# Arduino-Shield.net
KiCad netlist of a schematic drawn in EAGLE
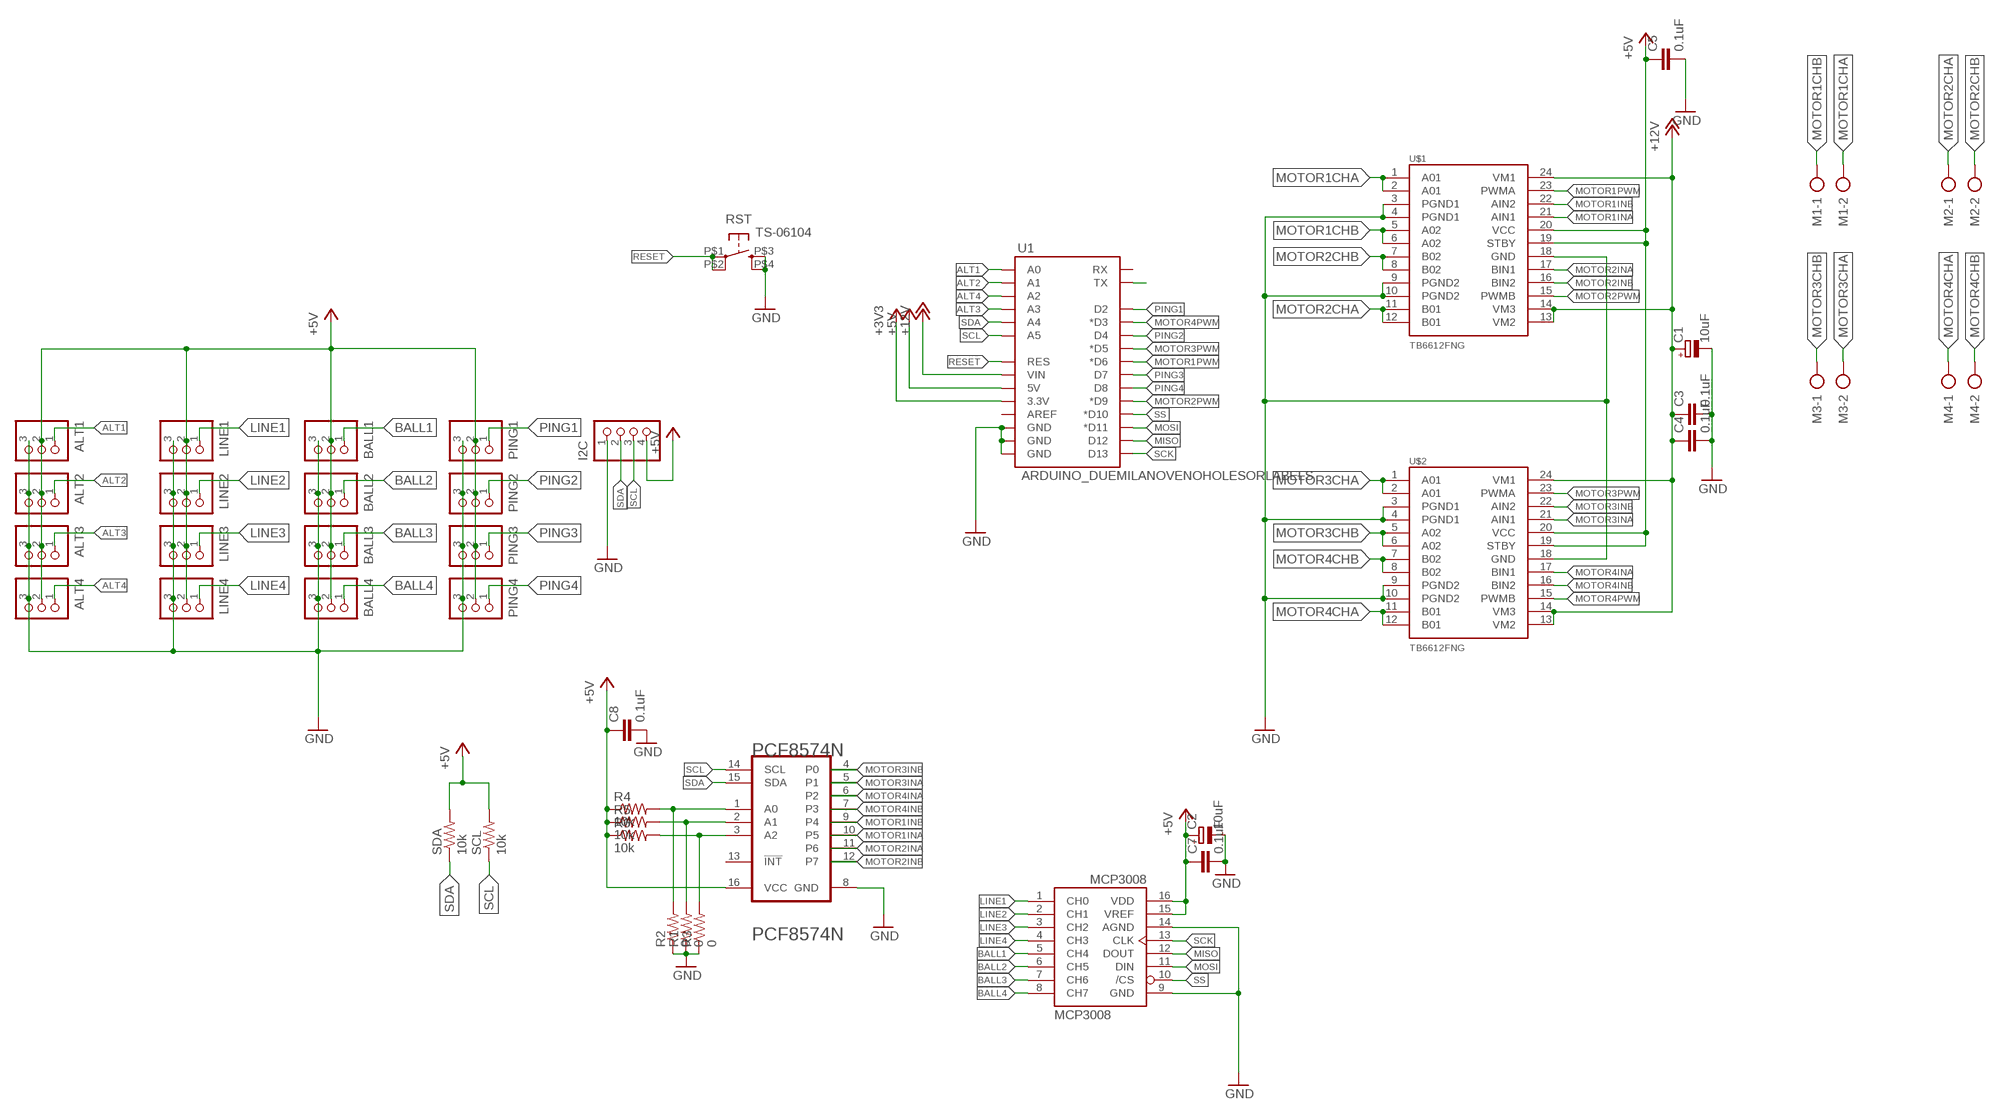
[diagram p0: schematic, sheet 1]

(export (version "E")
  (design (tool "Eeschema 10.0.6"))
  (components
    (comp (ref "ALT1")
      (value "B3B-XH-A")
      (footprint "eagle-import:B3B-XH-A")
      (libsource (lib "eagle-import") (part "B3B-XH-A"))
    )
    (comp (ref "ALT2")
      (value "B3B-XH-A")
      (footprint "eagle-import:B3B-XH-A")
      (libsource (lib "eagle-import") (part "B3B-XH-A"))
    )
    (comp (ref "ALT3")
      (value "B3B-XH-A")
      (footprint "eagle-import:B3B-XH-A")
      (libsource (lib "eagle-import") (part "B3B-XH-A"))
    )
    (comp (ref "ALT4")
      (value "B3B-XH-A")
      (footprint "eagle-import:B3B-XH-A")
      (libsource (lib "eagle-import") (part "B3B-XH-A"))
    )
    (comp (ref "BALL1")
      (value "B3B-XH-A")
      (footprint "eagle-import:B3B-XH-A")
      (libsource (lib "eagle-import") (part "B3B-XH-A"))
    )
    (comp (ref "BALL2")
      (value "B3B-XH-A")
      (footprint "eagle-import:B3B-XH-A")
      (libsource (lib "eagle-import") (part "B3B-XH-A"))
    )
    (comp (ref "BALL3")
      (value "B3B-XH-A")
      (footprint "eagle-import:B3B-XH-A")
      (libsource (lib "eagle-import") (part "B3B-XH-A"))
    )
    (comp (ref "BALL4")
      (value "B3B-XH-A")
      (footprint "eagle-import:B3B-XH-A")
      (libsource (lib "eagle-import") (part "B3B-XH-A"))
    )
    (comp (ref "C1")
      (value "10uF")
      (footprint "eagle-import:E2-5")
      (libsource (lib "eagle-import") (part "CPOL-EUE2-5"))
    )
    (comp (ref "C2")
      (value "10uF")
      (footprint "eagle-import:E2-5")
      (libsource (lib "eagle-import") (part "CPOL-EUE2-5"))
    )
    (comp (ref "C3")
      (value "0.1uF")
      (footprint "eagle-import:C1608")
      (libsource (lib "eagle-import") (part "C-EUC1608"))
    )
    (comp (ref "C4")
      (value "0.1uF")
      (footprint "eagle-import:C1608")
      (libsource (lib "eagle-import") (part "C-EUC1608"))
    )
    (comp (ref "C5")
      (value "0.1uF")
      (footprint "eagle-import:C1608")
      (libsource (lib "eagle-import") (part "C-EUC1608"))
    )
    (comp (ref "C7")
      (value "0.1uF")
      (footprint "eagle-import:C1608")
      (libsource (lib "eagle-import") (part "C-EUC1608"))
    )
    (comp (ref "C8")
      (value "0.1uF")
      (footprint "eagle-import:C1608")
      (libsource (lib "eagle-import") (part "C-EUC1608"))
    )
    (comp (ref "I2C")
      (value "B4B-XH-A")
      (footprint "eagle-import:B4B-XH-A")
      (libsource (lib "eagle-import") (part "B4B-XH-A"))
    )
    (comp (ref "LINE1")
      (value "B3B-XH-A")
      (footprint "eagle-import:B3B-XH-A")
      (libsource (lib "eagle-import") (part "B3B-XH-A"))
    )
    (comp (ref "LINE2")
      (value "B3B-XH-A")
      (footprint "eagle-import:B3B-XH-A")
      (libsource (lib "eagle-import") (part "B3B-XH-A"))
    )
    (comp (ref "LINE3")
      (value "B3B-XH-A")
      (footprint "eagle-import:B3B-XH-A")
      (libsource (lib "eagle-import") (part "B3B-XH-A"))
    )
    (comp (ref "LINE4")
      (value "B3B-XH-A")
      (footprint "eagle-import:B3B-XH-A")
      (libsource (lib "eagle-import") (part "B3B-XH-A"))
    )
    (comp (ref "M1")
      (value "AK500/2-H")
      (footprint "eagle-import:AK500_2-H")
      (libsource (lib "eagle-import") (part "AK500/2-H"))
    )
    (comp (ref "M2")
      (value "AK500/2-H")
      (footprint "eagle-import:AK500_2-H")
      (libsource (lib "eagle-import") (part "AK500/2-H"))
    )
    (comp (ref "M3")
      (value "AK500/2-H")
      (footprint "eagle-import:AK500_2-H")
      (libsource (lib "eagle-import") (part "AK500/2-H"))
    )
    (comp (ref "M4")
      (value "AK500/2-H")
      (footprint "eagle-import:AK500_2-H")
      (libsource (lib "eagle-import") (part "AK500/2-H"))
    )
    (comp (ref "MCP3008")
      (value "MCP3008")
      (footprint "eagle-import:DIL16")
      (libsource (lib "eagle-import") (part "MCP3008"))
    )
    (comp (ref "PCF8574N")
      (value "TEXAS_INSTRUMENTS_PCF8574NTEXAS_INSTRUMENTS_PCF8574N_0_0")
      (footprint "eagle-import:TEXAS_INSTRUMENTS_PCF8574N_0")
      (fields (field (name "MF") "Texas Instruments") (field (name "MPN") "PCF8574N"))
      (libsource (lib "eagle-import") (part "TEXAS_INSTRUMENTS_PCF8574NTEXAS_INSTRUMENTS_PCF8574N_0_0"))
    )
    (comp (ref "PING1")
      (value "B3B-XH-A")
      (footprint "eagle-import:B3B-XH-A")
      (libsource (lib "eagle-import") (part "B3B-XH-A"))
    )
    (comp (ref "PING2")
      (value "B3B-XH-A")
      (footprint "eagle-import:B3B-XH-A")
      (libsource (lib "eagle-import") (part "B3B-XH-A"))
    )
    (comp (ref "PING3")
      (value "B3B-XH-A")
      (footprint "eagle-import:B3B-XH-A")
      (libsource (lib "eagle-import") (part "B3B-XH-A"))
    )
    (comp (ref "PING4")
      (value "B3B-XH-A")
      (footprint "eagle-import:B3B-XH-A")
      (libsource (lib "eagle-import") (part "B3B-XH-A"))
    )
    (comp (ref "R1")
      (value "0")
      (footprint "eagle-import:M2012")
      (libsource (lib "eagle-import") (part "R-US_M2012"))
    )
    (comp (ref "R2")
      (value "0")
      (footprint "eagle-import:M2012")
      (libsource (lib "eagle-import") (part "R-US_M2012"))
    )
    (comp (ref "R3")
      (value "0")
      (footprint "eagle-import:M2012")
      (libsource (lib "eagle-import") (part "R-US_M2012"))
    )
    (comp (ref "R4")
      (value "10k")
      (footprint "eagle-import:R0603")
      (libsource (lib "eagle-import") (part "R-US_R0603"))
    )
    (comp (ref "R5")
      (value "10k")
      (footprint "eagle-import:R0603")
      (libsource (lib "eagle-import") (part "R-US_R0603"))
    )
    (comp (ref "R6")
      (value "10k")
      (footprint "eagle-import:R0603")
      (libsource (lib "eagle-import") (part "R-US_R0603"))
    )
    (comp (ref "RST")
      (value "TS-06104")
      (footprint "eagle-import:TS-06104")
      (libsource (lib "eagle-import") (part "TS-06104"))
    )
    (comp (ref "SCL")
      (value "10k")
      (footprint "eagle-import:R0603")
      (libsource (lib "eagle-import") (part "R-US_R0603"))
    )
    (comp (ref "SDA")
      (value "10k")
      (footprint "eagle-import:R0603")
      (libsource (lib "eagle-import") (part "R-US_R0603"))
    )
    (comp (ref "U$1")
      (value "TB6612FNG")
      (footprint "eagle-import:SSOP24")
      (libsource (lib "eagle-import") (part "TB6612FNG"))
    )
    (comp (ref "U$2")
      (value "TB6612FNG")
      (footprint "eagle-import:SSOP24")
      (libsource (lib "eagle-import") (part "TB6612FNG"))
    )
    (comp (ref "U1")
      (value "ARDUINO_DUEMILANOVENOHOLESORLABELS")
      (footprint "eagle-import:DUEMILANOVE_SHIELD_NOHOLES_NOLABELS")
      (libsource (lib "eagle-import") (part "ARDUINO_DUEMILANOVENOHOLESORLABELS"))
    )
  )
  (nets
    (net (code "1") (name "+3V3") (class "Default")
      (node (ref "U1") (pin "3.3V") (pinfunction "3.3V_3.3V") (pintype "bidirectional"))
    )
    (net (code "2") (name "+5V") (class "Default")
      (node (ref "ALT1") (pin "2") (pinfunction "2_2") (pintype "passive"))
      (node (ref "ALT2") (pin "2") (pinfunction "2_2") (pintype "passive"))
      (node (ref "ALT3") (pin "2") (pinfunction "2_2") (pintype "passive"))
      (node (ref "ALT4") (pin "2") (pinfunction "2_2") (pintype "passive"))
      (node (ref "BALL1") (pin "2") (pinfunction "2_2") (pintype "passive"))
      (node (ref "BALL2") (pin "2") (pinfunction "2_2") (pintype "passive"))
      (node (ref "BALL3") (pin "2") (pinfunction "2_2") (pintype "passive"))
      (node (ref "BALL4") (pin "2") (pinfunction "2_2") (pintype "passive"))
      (node (ref "C2") (pin "+") (pinfunction "+_+") (pintype "passive"))
      (node (ref "C5") (pin "1") (pinfunction "1_1") (pintype "passive"))
      (node (ref "C7") (pin "1") (pinfunction "1_1") (pintype "passive"))
      (node (ref "C8") (pin "1") (pinfunction "1_1") (pintype "passive"))
      (node (ref "I2C") (pin "4") (pinfunction "4_4") (pintype "passive"))
      (node (ref "LINE1") (pin "2") (pinfunction "2_2") (pintype "passive"))
      (node (ref "LINE2") (pin "2") (pinfunction "2_2") (pintype "passive"))
      (node (ref "LINE3") (pin "2") (pinfunction "2_2") (pintype "passive"))
      (node (ref "LINE4") (pin "2") (pinfunction "2_2") (pintype "passive"))
      (node (ref "MCP3008") (pin "15") (pinfunction "VREF_15") (pintype "input"))
      (node (ref "MCP3008") (pin "16") (pinfunction "VDD_16") (pintype "power_in"))
      (node (ref "PCF8574N") (pin "16") (pinfunction "VCC_16") (pintype "power_in"))
      (node (ref "PING1") (pin "2") (pinfunction "2_2") (pintype "passive"))
      (node (ref "PING2") (pin "2") (pinfunction "2_2") (pintype "passive"))
      (node (ref "PING3") (pin "2") (pinfunction "2_2") (pintype "passive"))
      (node (ref "PING4") (pin "2") (pinfunction "2_2") (pintype "passive"))
      (node (ref "R4") (pin "1") (pinfunction "1_1") (pintype "passive"))
      (node (ref "R5") (pin "1") (pinfunction "1_1") (pintype "passive"))
      (node (ref "R6") (pin "1") (pinfunction "1_1") (pintype "passive"))
      (node (ref "SCL") (pin "2") (pinfunction "2_2") (pintype "passive"))
      (node (ref "SDA") (pin "2") (pinfunction "2_2") (pintype "passive"))
      (node (ref "U$1") (pin "19") (pinfunction "STBY_19") (pintype "bidirectional"))
      (node (ref "U$1") (pin "20") (pinfunction "VCC_20") (pintype "bidirectional"))
      (node (ref "U$2") (pin "19") (pinfunction "STBY_19") (pintype "bidirectional"))
      (node (ref "U$2") (pin "20") (pinfunction "VCC_20") (pintype "bidirectional"))
      (node (ref "U1") (pin "5V") (pinfunction "5V_5V") (pintype "bidirectional"))
    )
    (net (code "3") (name "+12V") (class "Default")
      (node (ref "C1") (pin "+") (pinfunction "+_+") (pintype "passive"))
      (node (ref "C3") (pin "1") (pinfunction "1_1") (pintype "passive"))
      (node (ref "C4") (pin "1") (pinfunction "1_1") (pintype "passive"))
      (node (ref "U$1") (pin "13") (pinfunction "VM2_13") (pintype "bidirectional"))
      (node (ref "U$1") (pin "14") (pinfunction "VM3_14") (pintype "bidirectional"))
      (node (ref "U$1") (pin "24") (pinfunction "VM1_24") (pintype "bidirectional"))
      (node (ref "U$2") (pin "13") (pinfunction "VM2_13") (pintype "bidirectional"))
      (node (ref "U$2") (pin "14") (pinfunction "VM3_14") (pintype "bidirectional"))
      (node (ref "U$2") (pin "24") (pinfunction "VM1_24") (pintype "bidirectional"))
      (node (ref "U1") (pin "VIN") (pinfunction "VIN_VIN") (pintype "bidirectional"))
    )
    (net (code "4") (name "ALT1") (class "Default")
      (node (ref "ALT1") (pin "1") (pinfunction "1_1") (pintype "passive"))
      (node (ref "U1") (pin "A0") (pinfunction "A0_A0") (pintype "bidirectional"))
    )
    (net (code "5") (name "ALT2") (class "Default")
      (node (ref "ALT2") (pin "1") (pinfunction "1_1") (pintype "passive"))
      (node (ref "U1") (pin "A1") (pinfunction "A1_A1") (pintype "bidirectional"))
    )
    (net (code "6") (name "ALT3") (class "Default")
      (node (ref "ALT3") (pin "1") (pinfunction "1_1") (pintype "passive"))
      (node (ref "U1") (pin "A3") (pinfunction "A3_A3") (pintype "bidirectional"))
    )
    (net (code "7") (name "ALT4") (class "Default")
      (node (ref "ALT4") (pin "1") (pinfunction "1_1") (pintype "passive"))
      (node (ref "U1") (pin "A2") (pinfunction "A2_A2") (pintype "bidirectional"))
    )
    (net (code "8") (name "BALL1") (class "Default")
      (node (ref "BALL1") (pin "1") (pinfunction "1_1") (pintype "passive"))
      (node (ref "MCP3008") (pin "5") (pinfunction "CH4_5") (pintype "input"))
    )
    (net (code "9") (name "BALL2") (class "Default")
      (node (ref "BALL2") (pin "1") (pinfunction "1_1") (pintype "passive"))
      (node (ref "MCP3008") (pin "6") (pinfunction "CH5_6") (pintype "input"))
    )
    (net (code "10") (name "BALL3") (class "Default")
      (node (ref "BALL3") (pin "1") (pinfunction "1_1") (pintype "passive"))
      (node (ref "MCP3008") (pin "7") (pinfunction "CH6_7") (pintype "input"))
    )
    (net (code "11") (name "BALL4") (class "Default")
      (node (ref "BALL4") (pin "1") (pinfunction "1_1") (pintype "passive"))
      (node (ref "MCP3008") (pin "8") (pinfunction "CH7_8") (pintype "input"))
    )
    (net (code "12") (name "GND") (class "Default")
      (node (ref "ALT1") (pin "3") (pinfunction "3_3") (pintype "passive"))
      (node (ref "ALT2") (pin "3") (pinfunction "3_3") (pintype "passive"))
      (node (ref "ALT3") (pin "3") (pinfunction "3_3") (pintype "passive"))
      (node (ref "ALT4") (pin "3") (pinfunction "3_3") (pintype "passive"))
      (node (ref "BALL1") (pin "3") (pinfunction "3_3") (pintype "passive"))
      (node (ref "BALL2") (pin "3") (pinfunction "3_3") (pintype "passive"))
      (node (ref "BALL3") (pin "3") (pinfunction "3_3") (pintype "passive"))
      (node (ref "BALL4") (pin "3") (pinfunction "3_3") (pintype "passive"))
      (node (ref "C1") (pin "-") (pinfunction "-_-") (pintype "passive"))
      (node (ref "C2") (pin "-") (pinfunction "-_-") (pintype "passive"))
      (node (ref "C3") (pin "2") (pinfunction "2_2") (pintype "passive"))
      (node (ref "C4") (pin "2") (pinfunction "2_2") (pintype "passive"))
      (node (ref "C5") (pin "2") (pinfunction "2_2") (pintype "passive"))
      (node (ref "C7") (pin "2") (pinfunction "2_2") (pintype "passive"))
      (node (ref "C8") (pin "2") (pinfunction "2_2") (pintype "passive"))
      (node (ref "I2C") (pin "1") (pinfunction "1_1") (pintype "passive"))
      (node (ref "LINE1") (pin "3") (pinfunction "3_3") (pintype "passive"))
      (node (ref "LINE2") (pin "3") (pinfunction "3_3") (pintype "passive"))
      (node (ref "LINE3") (pin "3") (pinfunction "3_3") (pintype "passive"))
      (node (ref "LINE4") (pin "3") (pinfunction "3_3") (pintype "passive"))
      (node (ref "MCP3008") (pin "14") (pinfunction "AGND_14") (pintype "power_in"))
      (node (ref "MCP3008") (pin "9") (pinfunction "GND_9") (pintype "power_in"))
      (node (ref "PCF8574N") (pin "8") (pinfunction "GND_8") (pintype "power_in"))
      (node (ref "PING1") (pin "3") (pinfunction "3_3") (pintype "passive"))
      (node (ref "PING2") (pin "3") (pinfunction "3_3") (pintype "passive"))
      (node (ref "PING3") (pin "3") (pinfunction "3_3") (pintype "passive"))
      (node (ref "PING4") (pin "3") (pinfunction "3_3") (pintype "passive"))
      (node (ref "R1") (pin "1") (pinfunction "1_1") (pintype "passive"))
      (node (ref "R2") (pin "1") (pinfunction "1_1") (pintype "passive"))
      (node (ref "R3") (pin "1") (pinfunction "1_1") (pintype "passive"))
      (node (ref "RST") (pin "P$3") (pinfunction "3_P$3") (pintype "passive"))
      (node (ref "RST") (pin "P$4") (pinfunction "4_P$4") (pintype "passive"))
      (node (ref "U$1") (pin "10") (pinfunction "PGND2_10") (pintype "bidirectional"))
      (node (ref "U$1") (pin "18") (pinfunction "GND_18") (pintype "bidirectional"))
      (node (ref "U$1") (pin "3") (pinfunction "PGND1_3") (pintype "bidirectional"))
      (node (ref "U$1") (pin "4") (pinfunction "PGND1_4") (pintype "bidirectional"))
      (node (ref "U$1") (pin "9") (pinfunction "PGND2_9") (pintype "bidirectional"))
      (node (ref "U$2") (pin "10") (pinfunction "PGND2_10") (pintype "bidirectional"))
      (node (ref "U$2") (pin "18") (pinfunction "GND_18") (pintype "bidirectional"))
      (node (ref "U$2") (pin "3") (pinfunction "PGND1_3") (pintype "bidirectional"))
      (node (ref "U$2") (pin "4") (pinfunction "PGND1_4") (pintype "bidirectional"))
      (node (ref "U$2") (pin "9") (pinfunction "PGND2_9") (pintype "bidirectional"))
      (node (ref "U1") (pin "GND@0") (pinfunction "GND_GND@0") (pintype "bidirectional"))
      (node (ref "U1") (pin "GND@1") (pinfunction "GND_GND@1") (pintype "bidirectional"))
      (node (ref "U1") (pin "GND@2") (pinfunction "GND_GND@2") (pintype "bidirectional"))
    )
    (net (code "13") (name "LINE1") (class "Default")
      (node (ref "LINE1") (pin "1") (pinfunction "1_1") (pintype "passive"))
      (node (ref "MCP3008") (pin "1") (pinfunction "CH0_1") (pintype "input"))
    )
    (net (code "14") (name "LINE2") (class "Default")
      (node (ref "LINE2") (pin "1") (pinfunction "1_1") (pintype "passive"))
      (node (ref "MCP3008") (pin "2") (pinfunction "CH1_2") (pintype "input"))
    )
    (net (code "15") (name "LINE3") (class "Default")
      (node (ref "LINE3") (pin "1") (pinfunction "1_1") (pintype "passive"))
      (node (ref "MCP3008") (pin "3") (pinfunction "CH2_3") (pintype "input"))
    )
    (net (code "16") (name "LINE4") (class "Default")
      (node (ref "LINE4") (pin "1") (pinfunction "1_1") (pintype "passive"))
      (node (ref "MCP3008") (pin "4") (pinfunction "CH3_4") (pintype "input"))
    )
    (net (code "17") (name "MISO") (class "Default")
      (node (ref "MCP3008") (pin "12") (pinfunction "DOUT_12") (pintype "output"))
      (node (ref "U1") (pin "D12") (pinfunction "D12_D12") (pintype "bidirectional"))
    )
    (net (code "18") (name "MOSI") (class "Default")
      (node (ref "MCP3008") (pin "11") (pinfunction "DIN_11") (pintype "input"))
      (node (ref "U1") (pin "D11") (pinfunction "*D11_D11") (pintype "bidirectional"))
    )
    (net (code "19") (name "MOTOR1CHA") (class "Default")
      (node (ref "M1") (pin "2") (pinfunction "KL_2") (pintype "passive"))
      (node (ref "U$1") (pin "1") (pinfunction "A01_1") (pintype "bidirectional"))
      (node (ref "U$1") (pin "2") (pinfunction "A01_2") (pintype "bidirectional"))
    )
    (net (code "20") (name "MOTOR1CHB") (class "Default")
      (node (ref "M1") (pin "1") (pinfunction "KL_1") (pintype "passive"))
      (node (ref "U$1") (pin "5") (pinfunction "A02_5") (pintype "bidirectional"))
      (node (ref "U$1") (pin "6") (pinfunction "A02_6") (pintype "bidirectional"))
    )
    (net (code "21") (name "MOTOR1INA") (class "Default")
      (node (ref "PCF8574N") (pin "10") (pinfunction "P5_10") (pintype "bidirectional"))
      (node (ref "U$1") (pin "21") (pinfunction "AIN1_21") (pintype "bidirectional"))
    )
    (net (code "22") (name "MOTOR1INB") (class "Default")
      (node (ref "PCF8574N") (pin "9") (pinfunction "P4_9") (pintype "bidirectional"))
      (node (ref "U$1") (pin "22") (pinfunction "AIN2_22") (pintype "bidirectional"))
    )
    (net (code "23") (name "MOTOR1PWM") (class "Default")
      (node (ref "U$1") (pin "23") (pinfunction "PWMA_23") (pintype "bidirectional"))
      (node (ref "U1") (pin "D6") (pinfunction "*D6_D6") (pintype "bidirectional"))
    )
    (net (code "24") (name "MOTOR2CHA") (class "Default")
      (node (ref "M2") (pin "1") (pinfunction "KL_1") (pintype "passive"))
      (node (ref "U$1") (pin "11") (pinfunction "B01_11") (pintype "bidirectional"))
      (node (ref "U$1") (pin "12") (pinfunction "B01_12") (pintype "bidirectional"))
    )
    (net (code "25") (name "MOTOR2CHB") (class "Default")
      (node (ref "M2") (pin "2") (pinfunction "KL_2") (pintype "passive"))
      (node (ref "U$1") (pin "7") (pinfunction "B02_7") (pintype "bidirectional"))
      (node (ref "U$1") (pin "8") (pinfunction "B02_8") (pintype "bidirectional"))
    )
    (net (code "26") (name "MOTOR2INA") (class "Default")
      (node (ref "PCF8574N") (pin "11") (pinfunction "P6_11") (pintype "bidirectional"))
      (node (ref "U$1") (pin "17") (pinfunction "BIN1_17") (pintype "bidirectional"))
    )
    (net (code "27") (name "MOTOR2INB") (class "Default")
      (node (ref "PCF8574N") (pin "12") (pinfunction "P7_12") (pintype "bidirectional"))
      (node (ref "U$1") (pin "16") (pinfunction "BIN2_16") (pintype "bidirectional"))
    )
    (net (code "28") (name "MOTOR2PWM") (class "Default")
      (node (ref "U$1") (pin "15") (pinfunction "PWMB_15") (pintype "bidirectional"))
      (node (ref "U1") (pin "D9") (pinfunction "*D9_D9") (pintype "bidirectional"))
    )
    (net (code "29") (name "MOTOR3CHA") (class "Default")
      (node (ref "M3") (pin "2") (pinfunction "KL_2") (pintype "passive"))
      (node (ref "U$2") (pin "1") (pinfunction "A01_1") (pintype "bidirectional"))
      (node (ref "U$2") (pin "2") (pinfunction "A01_2") (pintype "bidirectional"))
    )
    (net (code "30") (name "MOTOR3CHB") (class "Default")
      (node (ref "M3") (pin "1") (pinfunction "KL_1") (pintype "passive"))
      (node (ref "U$2") (pin "5") (pinfunction "A02_5") (pintype "bidirectional"))
      (node (ref "U$2") (pin "6") (pinfunction "A02_6") (pintype "bidirectional"))
    )
    (net (code "31") (name "MOTOR3INA") (class "Default")
      (node (ref "PCF8574N") (pin "5") (pinfunction "P1_5") (pintype "bidirectional"))
      (node (ref "U$2") (pin "21") (pinfunction "AIN1_21") (pintype "bidirectional"))
    )
    (net (code "32") (name "MOTOR3INB") (class "Default")
      (node (ref "PCF8574N") (pin "4") (pinfunction "P0_4") (pintype "bidirectional"))
      (node (ref "U$2") (pin "22") (pinfunction "AIN2_22") (pintype "bidirectional"))
    )
    (net (code "33") (name "MOTOR3PWM") (class "Default")
      (node (ref "U$2") (pin "23") (pinfunction "PWMA_23") (pintype "bidirectional"))
      (node (ref "U1") (pin "D5") (pinfunction "*D5_D5") (pintype "bidirectional"))
    )
    (net (code "34") (name "MOTOR4CHA") (class "Default")
      (node (ref "M4") (pin "1") (pinfunction "KL_1") (pintype "passive"))
      (node (ref "U$2") (pin "11") (pinfunction "B01_11") (pintype "bidirectional"))
      (node (ref "U$2") (pin "12") (pinfunction "B01_12") (pintype "bidirectional"))
    )
    (net (code "35") (name "MOTOR4CHB") (class "Default")
      (node (ref "M4") (pin "2") (pinfunction "KL_2") (pintype "passive"))
      (node (ref "U$2") (pin "7") (pinfunction "B02_7") (pintype "bidirectional"))
      (node (ref "U$2") (pin "8") (pinfunction "B02_8") (pintype "bidirectional"))
    )
    (net (code "36") (name "MOTOR4INA") (class "Default")
      (node (ref "PCF8574N") (pin "6") (pinfunction "P2_6") (pintype "bidirectional"))
      (node (ref "U$2") (pin "17") (pinfunction "BIN1_17") (pintype "bidirectional"))
    )
    (net (code "37") (name "MOTOR4INB") (class "Default")
      (node (ref "PCF8574N") (pin "7") (pinfunction "P3_7") (pintype "bidirectional"))
      (node (ref "U$2") (pin "16") (pinfunction "BIN2_16") (pintype "bidirectional"))
    )
    (net (code "38") (name "MOTOR4PWM") (class "Default")
      (node (ref "U$2") (pin "15") (pinfunction "PWMB_15") (pintype "bidirectional"))
      (node (ref "U1") (pin "D3") (pinfunction "*D3_D3") (pintype "bidirectional"))
    )
    (net (code "39") (name "Net-(PCF8574N-A0)") (class "Default")
      (node (ref "PCF8574N") (pin "1") (pinfunction "A0_1") (pintype "input"))
      (node (ref "R2") (pin "2") (pinfunction "2_2") (pintype "passive"))
      (node (ref "R4") (pin "2") (pinfunction "2_2") (pintype "passive"))
    )
    (net (code "40") (name "Net-(PCF8574N-A1)") (class "Default")
      (node (ref "PCF8574N") (pin "2") (pinfunction "A1_2") (pintype "input"))
      (node (ref "R1") (pin "2") (pinfunction "2_2") (pintype "passive"))
      (node (ref "R5") (pin "2") (pinfunction "2_2") (pintype "passive"))
    )
    (net (code "41") (name "Net-(PCF8574N-A2)") (class "Default")
      (node (ref "PCF8574N") (pin "3") (pinfunction "A2_3") (pintype "input"))
      (node (ref "R3") (pin "2") (pinfunction "2_2") (pintype "passive"))
      (node (ref "R6") (pin "2") (pinfunction "2_2") (pintype "passive"))
    )
    (net (code "42") (name "PING1") (class "Default")
      (node (ref "PING1") (pin "1") (pinfunction "1_1") (pintype "passive"))
      (node (ref "U1") (pin "D2") (pinfunction "D2_D2") (pintype "bidirectional"))
    )
    (net (code "43") (name "PING2") (class "Default")
      (node (ref "PING2") (pin "1") (pinfunction "1_1") (pintype "passive"))
      (node (ref "U1") (pin "D4") (pinfunction "D4_D4") (pintype "bidirectional"))
    )
    (net (code "44") (name "PING3") (class "Default")
      (node (ref "PING3") (pin "1") (pinfunction "1_1") (pintype "passive"))
      (node (ref "U1") (pin "D7") (pinfunction "D7_D7") (pintype "bidirectional"))
    )
    (net (code "45") (name "PING4") (class "Default")
      (node (ref "PING4") (pin "1") (pinfunction "1_1") (pintype "passive"))
      (node (ref "U1") (pin "D8") (pinfunction "D8_D8") (pintype "bidirectional"))
    )
    (net (code "46") (name "RESET") (class "Default")
      (node (ref "RST") (pin "P$1") (pinfunction "1_P$1") (pintype "passive"))
      (node (ref "RST") (pin "P$2") (pinfunction "2_P$2") (pintype "passive"))
      (node (ref "U1") (pin "RES") (pinfunction "RES_RES") (pintype "bidirectional"))
    )
    (net (code "47") (name "SCK") (class "Default")
      (node (ref "MCP3008") (pin "13") (pinfunction "CLK_13") (pintype "input"))
      (node (ref "U1") (pin "D13") (pinfunction "D13_D13") (pintype "bidirectional"))
    )
    (net (code "48") (name "SCL") (class "Default")
      (node (ref "I2C") (pin "3") (pinfunction "3_3") (pintype "passive"))
      (node (ref "PCF8574N") (pin "14") (pinfunction "SCL_14") (pintype "input"))
      (node (ref "SCL") (pin "1") (pinfunction "1_1") (pintype "passive"))
      (node (ref "U1") (pin "A5") (pinfunction "A5_A5") (pintype "bidirectional"))
    )
    (net (code "49") (name "SDA") (class "Default")
      (node (ref "I2C") (pin "2") (pinfunction "2_2") (pintype "passive"))
      (node (ref "PCF8574N") (pin "15") (pinfunction "SDA_15") (pintype "bidirectional"))
      (node (ref "SDA") (pin "1") (pinfunction "1_1") (pintype "passive"))
      (node (ref "U1") (pin "A4") (pinfunction "A4_A4") (pintype "bidirectional"))
    )
    (net (code "50") (name "SS") (class "Default")
      (node (ref "MCP3008") (pin "10") (pinfunction "/CS_10") (pintype "input"))
      (node (ref "U1") (pin "D10") (pinfunction "*D10_D10") (pintype "bidirectional"))
    )
    (net (code "51") (name "unconnected-(PCF8574N-~{INT}-Pad13)") (class "Default")
      (node (ref "PCF8574N") (pin "13") (pinfunction "~{INT}_13") (pintype "open_collector"))
    )
    (net (code "52") (name "unconnected-(U1-PadAREF)") (class "Default")
      (node (ref "U1") (pin "AREF") (pinfunction "AREF_AREF") (pintype "bidirectional"))
    )
    (net (code "53") (name "unconnected-(U1-PadRX)") (class "Default")
      (node (ref "U1") (pin "RX") (pinfunction "RX_RX") (pintype "bidirectional"))
    )
    (net (code "54") (name "unconnected-(U1-PadTX)") (class "Default")
      (node (ref "U1") (pin "TX") (pinfunction "TX_TX") (pintype "bidirectional"))
    )
  )
)
